# drum_circuits.net
KiCad netlist of a schematic drawn in EAGLE
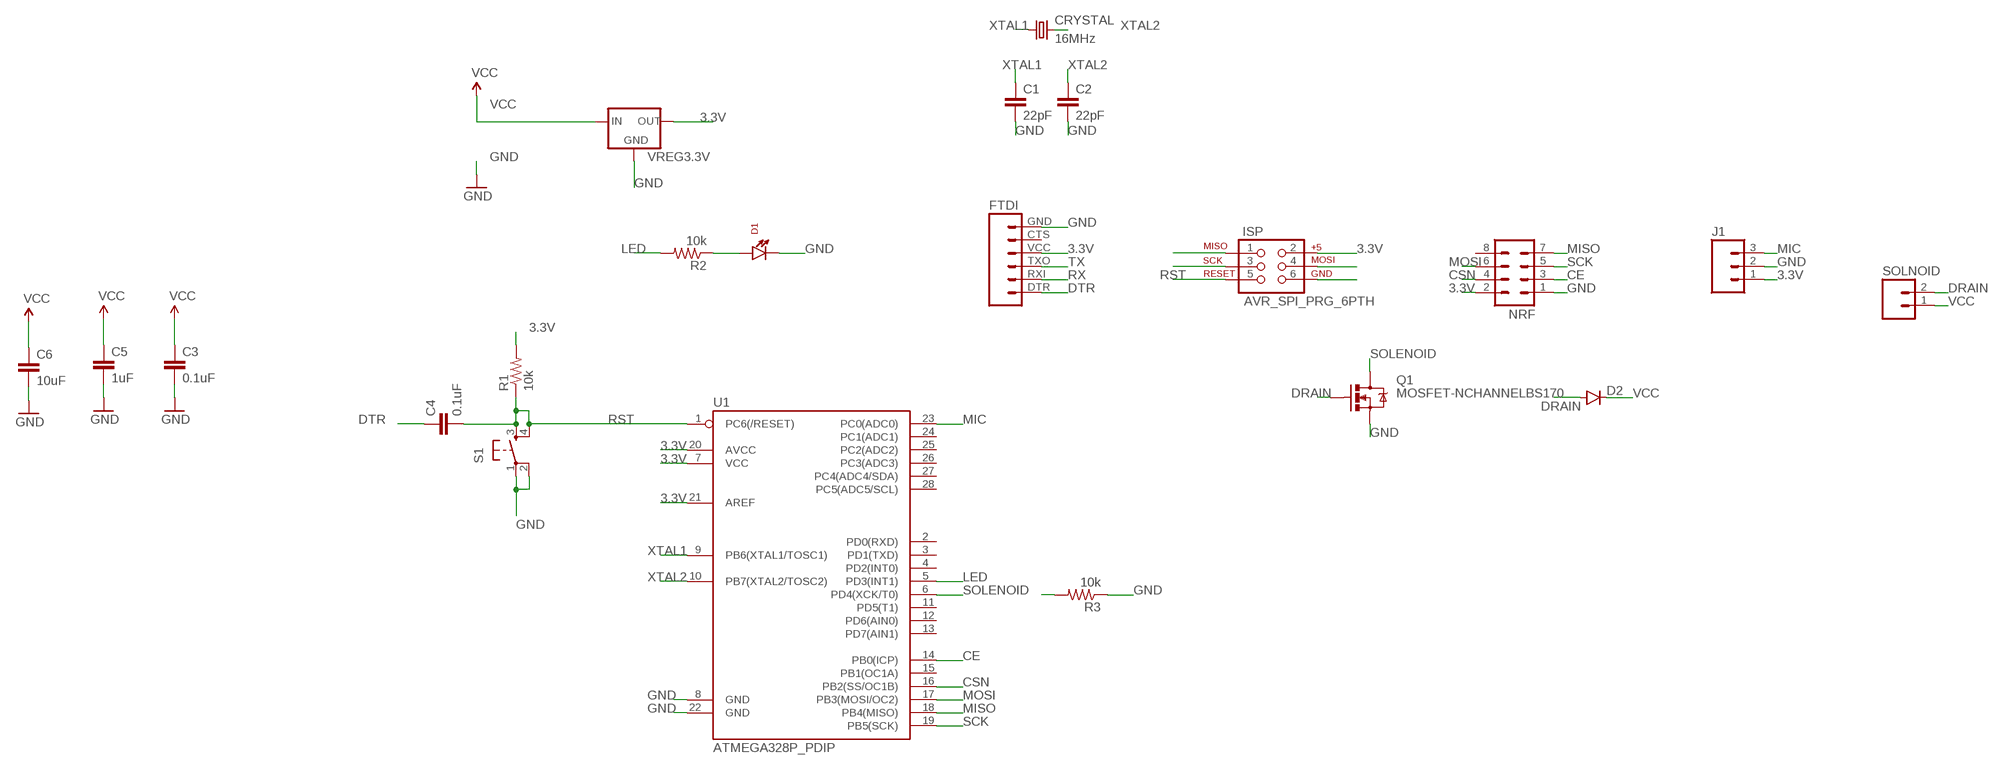
[diagram p0: schematic, sheet 1]

(export (version "E")
  (design (tool "Eeschema 10.0.6"))
  (components
    (comp (ref "C1")
      (value "22pF")
      (footprint "eagle-import:CAP-PTH-SMALL2")
      (libsource (lib "eagle-import") (part "CAPPTH2"))
    )
    (comp (ref "C2")
      (value "22pF")
      (footprint "eagle-import:CAP-PTH-SMALL2")
      (libsource (lib "eagle-import") (part "CAPPTH2"))
    )
    (comp (ref "C3")
      (value "0.1uF")
      (footprint "eagle-import:CAP-PTH-SMALL")
      (libsource (lib "eagle-import") (part "SparkFun-Passives_CAPPTH"))
    )
    (comp (ref "C4")
      (value "0.1uF")
      (footprint "eagle-import:CAP-PTH-SMALL")
      (libsource (lib "eagle-import") (part "SparkFun-Passives_CAPPTH"))
    )
    (comp (ref "C5")
      (value "1uF")
      (footprint "eagle-import:CAP-PTH-SMALL")
      (libsource (lib "eagle-import") (part "SparkFun-Passives_CAPPTH"))
    )
    (comp (ref "C6")
      (value "10uF")
      (footprint "eagle-import:CAP-PTH-SMALL")
      (libsource (lib "eagle-import") (part "SparkFun-Passives_CAPPTH"))
    )
    (comp (ref "CRYSTAL")
      (value "16MHz")
      (footprint "eagle-import:HC49US")
      (libsource (lib "eagle-import") (part "CRYSTALHC49US"))
    )
    (comp (ref "D1")
      (value "LTE-302")
      (footprint "eagle-import:LTE-302")
      (libsource (lib "eagle-import") (part "LTE-302"))
    )
    (comp (ref "D2")
      (value "DIODEKIT2")
      (footprint "eagle-import:DIODE-1N4001-KIT")
      (libsource (lib "eagle-import") (part "DIODEKIT2"))
    )
    (comp (ref "FTDI")
      (value "FTDI_BASICPTH")
      (footprint "eagle-import:FTDI_BASIC")
      (libsource (lib "eagle-import") (part "FTDI_BASICPTH"))
    )
    (comp (ref "ISP")
      (value "AVR_SPI_PRG_6PTH")
      (footprint "eagle-import:2X3")
      (libsource (lib "eagle-import") (part "AVR_SPI_PRG_6PTH"))
    )
    (comp (ref "J1")
      (value "M03PTH")
      (footprint "eagle-import:1X03")
      (libsource (lib "eagle-import") (part "M03PTH"))
    )
    (comp (ref "NRF")
      (value "M04X2")
      (footprint "eagle-import:2X4")
      (libsource (lib "eagle-import") (part "M04X2"))
    )
    (comp (ref "Q1")
      (value "MOSFET-NCHANNELBS170")
      (footprint "eagle-import:TO-92")
      (libsource (lib "eagle-import") (part "MOSFET-NCHANNELBS170"))
    )
    (comp (ref "R1")
      (value "10k")
      (footprint "eagle-import:AXIAL-0.3EZ")
      (libsource (lib "eagle-import") (part "10KOHM-1/4W-1%(PTH)HORIZ-KIT"))
    )
    (comp (ref "R2")
      (value "10k")
      (footprint "eagle-import:AXIAL-0.3EZ")
      (libsource (lib "eagle-import") (part "10KOHM-1/4W-1%(PTH)HORIZ-KIT"))
    )
    (comp (ref "R3")
      (value "10k")
      (footprint "eagle-import:AXIAL-0.3EZ")
      (libsource (lib "eagle-import") (part "10KOHM-1/4W-1%(PTH)HORIZ-KIT"))
    )
    (comp (ref "S1")
      (value "TAC_SWITCHPTH")
      (footprint "eagle-import:TACTILE-PTH")
      (libsource (lib "eagle-import") (part "TAC_SWITCHPTH"))
    )
    (comp (ref "SOLNOID")
      (value "M02PTH")
      (footprint "eagle-import:1X02")
      (libsource (lib "eagle-import") (part "M02PTH"))
    )
    (comp (ref "U1")
      (value "ATMEGA328P_PDIP")
      (footprint "eagle-import:DIL28-3")
      (libsource (lib "eagle-import") (part "ATMEGA328P_PDIP"))
    )
    (comp (ref "VREG3.3V")
      (value "V_REG_78XX-TO-220")
      (footprint "eagle-import:TO-220-ALT")
      (libsource (lib "eagle-import") (part "V_REG_78XX-TO-220"))
    )
  )
  (nets
    (net (code "1") (name "/3.3V") (class "Default")
      (node (ref "FTDI") (pin "VCC") (pinfunction "4_VCC") (pintype "passive"))
      (node (ref "ISP") (pin "2") (pinfunction "2_2") (pintype "passive"))
      (node (ref "J1") (pin "1") (pinfunction "1_1") (pintype "passive"))
      (node (ref "NRF") (pin "2") (pinfunction "2_2") (pintype "passive"))
      (node (ref "R1") (pin "P$2") (pinfunction "2_P$2") (pintype "passive"))
      (node (ref "U1") (pin "20") (pinfunction "AVCC_20") (pintype "bidirectional"))
      (node (ref "U1") (pin "21") (pinfunction "AREF_21") (pintype "bidirectional"))
      (node (ref "U1") (pin "7") (pinfunction "VCC_7") (pintype "bidirectional"))
      (node (ref "VREG3.3V") (pin "OUT") (pinfunction "OUT_OUT") (pintype "passive"))
    )
    (net (code "2") (name "/CE") (class "Default")
      (node (ref "NRF") (pin "3") (pinfunction "3_3") (pintype "passive"))
      (node (ref "U1") (pin "14") (pinfunction "PB0(ICP)_14") (pintype "bidirectional"))
    )
    (net (code "3") (name "/CSN") (class "Default")
      (node (ref "NRF") (pin "4") (pinfunction "4_4") (pintype "passive"))
      (node (ref "U1") (pin "16") (pinfunction "PB2(SS/OC1B)_16") (pintype "bidirectional"))
    )
    (net (code "4") (name "/DRAIN") (class "Default")
      (node (ref "D2") (pin "A") (pinfunction "A_A") (pintype "passive"))
      (node (ref "Q1") (pin "2") (pinfunction "G_2") (pintype "passive"))
      (node (ref "SOLNOID") (pin "2") (pinfunction "2_2") (pintype "passive"))
    )
    (net (code "5") (name "/DTR") (class "Default")
      (node (ref "C4") (pin "1") (pinfunction "1_1") (pintype "passive"))
      (node (ref "FTDI") (pin "DTR") (pinfunction "1_DTR") (pintype "passive"))
    )
    (net (code "6") (name "/LED") (class "Default")
      (node (ref "R2") (pin "P$2") (pinfunction "2_P$2") (pintype "passive"))
      (node (ref "U1") (pin "5") (pinfunction "PD3(INT1)_5") (pintype "bidirectional"))
    )
    (net (code "7") (name "/MIC") (class "Default")
      (node (ref "J1") (pin "3") (pinfunction "3_3") (pintype "passive"))
      (node (ref "U1") (pin "23") (pinfunction "PC0(ADC0)_23") (pintype "bidirectional"))
    )
    (net (code "8") (name "/MISO") (class "Default")
      (node (ref "ISP") (pin "1") (pinfunction "1_1") (pintype "passive"))
      (node (ref "NRF") (pin "7") (pinfunction "7_7") (pintype "passive"))
      (node (ref "U1") (pin "18") (pinfunction "PB4(MISO)_18") (pintype "bidirectional"))
    )
    (net (code "9") (name "/MOSI") (class "Default")
      (node (ref "ISP") (pin "4") (pinfunction "4_4") (pintype "passive"))
      (node (ref "NRF") (pin "6") (pinfunction "6_6") (pintype "passive"))
      (node (ref "U1") (pin "17") (pinfunction "PB3(MOSI/OC2)_17") (pintype "bidirectional"))
    )
    (net (code "10") (name "/RST") (class "Default")
      (node (ref "C4") (pin "2") (pinfunction "2_2") (pintype "passive"))
      (node (ref "ISP") (pin "5") (pinfunction "5_5") (pintype "passive"))
      (node (ref "R1") (pin "P$1") (pinfunction "1_P$1") (pintype "passive"))
      (node (ref "S1") (pin "3") (pinfunction "3_3") (pintype "passive"))
      (node (ref "S1") (pin "4") (pinfunction "4_4") (pintype "passive"))
      (node (ref "U1") (pin "1") (pinfunction "PC6(/RESET)_1") (pintype "bidirectional"))
    )
    (net (code "11") (name "/RX") (class "Default")
      (node (ref "FTDI") (pin "RXI") (pinfunction "2_RXI") (pintype "passive"))
    )
    (net (code "12") (name "/SCK") (class "Default")
      (node (ref "ISP") (pin "3") (pinfunction "3_3") (pintype "passive"))
      (node (ref "NRF") (pin "5") (pinfunction "5_5") (pintype "passive"))
      (node (ref "U1") (pin "19") (pinfunction "PB5(SCK)_19") (pintype "bidirectional"))
    )
    (net (code "13") (name "/SOLENOID") (class "Default")
      (node (ref "Q1") (pin "1") (pinfunction "D_1") (pintype "passive"))
      (node (ref "R3") (pin "P$2") (pinfunction "2_P$2") (pintype "passive"))
      (node (ref "U1") (pin "6") (pinfunction "PD4(XCK/T0)_6") (pintype "bidirectional"))
    )
    (net (code "14") (name "/TX") (class "Default")
      (node (ref "FTDI") (pin "TXO") (pinfunction "3_TXO") (pintype "passive"))
    )
    (net (code "15") (name "/XTAL1") (class "Default")
      (node (ref "C1") (pin "1") (pinfunction "1_1") (pintype "passive"))
      (node (ref "CRYSTAL") (pin "1") (pinfunction "1_1") (pintype "passive"))
      (node (ref "U1") (pin "9") (pinfunction "PB6(XTAL1/TOSC1)_9") (pintype "bidirectional"))
    )
    (net (code "16") (name "/XTAL2") (class "Default")
      (node (ref "C2") (pin "1") (pinfunction "1_1") (pintype "passive"))
      (node (ref "CRYSTAL") (pin "2") (pinfunction "2_2") (pintype "passive"))
      (node (ref "U1") (pin "10") (pinfunction "PB7(XTAL2/TOSC2)_10") (pintype "bidirectional"))
    )
    (net (code "17") (name "GND") (class "Default")
      (node (ref "C1") (pin "2") (pinfunction "2_2") (pintype "passive"))
      (node (ref "C2") (pin "2") (pinfunction "2_2") (pintype "passive"))
      (node (ref "C3") (pin "2") (pinfunction "2_2") (pintype "passive"))
      (node (ref "C5") (pin "2") (pinfunction "2_2") (pintype "passive"))
      (node (ref "C6") (pin "2") (pinfunction "2_2") (pintype "passive"))
      (node (ref "D1") (pin "C") (pinfunction "C_C") (pintype "bidirectional"))
      (node (ref "FTDI") (pin "GND") (pinfunction "6_GND") (pintype "passive"))
      (node (ref "ISP") (pin "6") (pinfunction "6_6") (pintype "passive"))
      (node (ref "J1") (pin "2") (pinfunction "2_2") (pintype "passive"))
      (node (ref "NRF") (pin "1") (pinfunction "1_1") (pintype "passive"))
      (node (ref "Q1") (pin "3") (pinfunction "S_3") (pintype "passive"))
      (node (ref "R3") (pin "P$1") (pinfunction "1_P$1") (pintype "passive"))
      (node (ref "S1") (pin "1") (pinfunction "1_1") (pintype "passive"))
      (node (ref "S1") (pin "2") (pinfunction "2_2") (pintype "passive"))
      (node (ref "U1") (pin "22") (pinfunction "GND_22") (pintype "bidirectional"))
      (node (ref "U1") (pin "8") (pinfunction "GND_8") (pintype "bidirectional"))
      (node (ref "VREG3.3V") (pin "GND") (pinfunction "GND_GND") (pintype "input"))
    )
    (net (code "18") (name "Net-(R2-1)") (class "Default")
      (node (ref "D1") (pin "A") (pinfunction "A_A") (pintype "bidirectional"))
      (node (ref "R2") (pin "P$1") (pinfunction "1_P$1") (pintype "passive"))
    )
    (net (code "19") (name "VCC") (class "Default")
      (node (ref "C3") (pin "1") (pinfunction "1_1") (pintype "passive"))
      (node (ref "C5") (pin "1") (pinfunction "1_1") (pintype "passive"))
      (node (ref "C6") (pin "1") (pinfunction "1_1") (pintype "passive"))
      (node (ref "D2") (pin "C") (pinfunction "C_C") (pintype "passive"))
      (node (ref "SOLNOID") (pin "1") (pinfunction "1_1") (pintype "passive"))
      (node (ref "VREG3.3V") (pin "IN") (pinfunction "IN_IN") (pintype "input"))
    )
    (net (code "20") (name "unconnected-(FTDI-5-PadCTS)") (class "Default")
      (node (ref "FTDI") (pin "CTS") (pinfunction "5_CTS") (pintype "passive"))
    )
    (net (code "21") (name "unconnected-(NRF-Pad8)") (class "Default")
      (node (ref "NRF") (pin "8") (pinfunction "8_8") (pintype "passive"))
    )
    (net (code "22") (name "unconnected-(U1-PB1(OC1A)-Pad15)") (class "Default")
      (node (ref "U1") (pin "15") (pinfunction "PB1(OC1A)_15") (pintype "bidirectional"))
    )
    (net (code "23") (name "unconnected-(U1-PC1(ADC1)-Pad24)") (class "Default")
      (node (ref "U1") (pin "24") (pinfunction "PC1(ADC1)_24") (pintype "bidirectional"))
    )
    (net (code "24") (name "unconnected-(U1-PC2(ADC2)-Pad25)") (class "Default")
      (node (ref "U1") (pin "25") (pinfunction "PC2(ADC2)_25") (pintype "bidirectional"))
    )
    (net (code "25") (name "unconnected-(U1-PC3(ADC3)-Pad26)") (class "Default")
      (node (ref "U1") (pin "26") (pinfunction "PC3(ADC3)_26") (pintype "bidirectional"))
    )
    (net (code "26") (name "unconnected-(U1-PC4(ADC4{slash}SDA)-Pad27)") (class "Default")
      (node (ref "U1") (pin "27") (pinfunction "PC4(ADC4/SDA)_27") (pintype "bidirectional"))
    )
    (net (code "27") (name "unconnected-(U1-PC5(ADC5{slash}SCL)-Pad28)") (class "Default")
      (node (ref "U1") (pin "28") (pinfunction "PC5(ADC5/SCL)_28") (pintype "bidirectional"))
    )
    (net (code "28") (name "unconnected-(U1-PD0(RXD)-Pad2)") (class "Default")
      (node (ref "U1") (pin "2") (pinfunction "PD0(RXD)_2") (pintype "bidirectional"))
    )
    (net (code "29") (name "unconnected-(U1-PD1(TXD)-Pad3)") (class "Default")
      (node (ref "U1") (pin "3") (pinfunction "PD1(TXD)_3") (pintype "bidirectional"))
    )
    (net (code "30") (name "unconnected-(U1-PD2(INT0)-Pad4)") (class "Default")
      (node (ref "U1") (pin "4") (pinfunction "PD2(INT0)_4") (pintype "bidirectional"))
    )
    (net (code "31") (name "unconnected-(U1-PD5(T1)-Pad11)") (class "Default")
      (node (ref "U1") (pin "11") (pinfunction "PD5(T1)_11") (pintype "bidirectional"))
    )
    (net (code "32") (name "unconnected-(U1-PD6(AIN0)-Pad12)") (class "Default")
      (node (ref "U1") (pin "12") (pinfunction "PD6(AIN0)_12") (pintype "bidirectional"))
    )
    (net (code "33") (name "unconnected-(U1-PD7(AIN1)-Pad13)") (class "Default")
      (node (ref "U1") (pin "13") (pinfunction "PD7(AIN1)_13") (pintype "bidirectional"))
    )
  )
)
